# main.net
KiCad netlist of a schematic drawn in Altium Designer
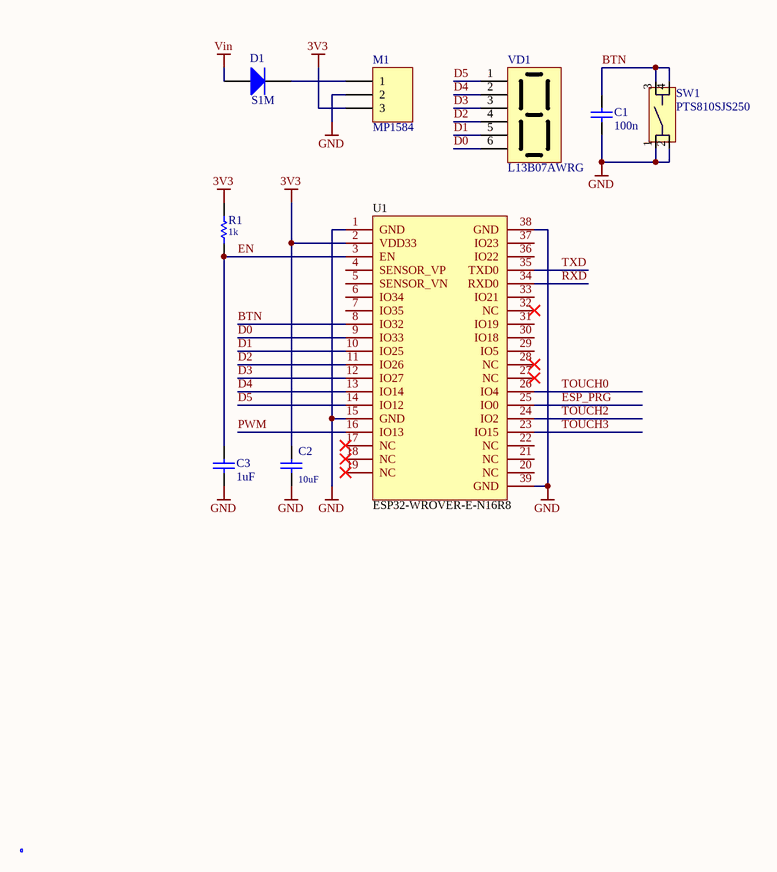
[diagram p0: main.SchDoc]

(export (version "E")
  (design (tool "Eeschema 10.0.6"))
  (components
    (comp (ref "C1")
      (value "100n")
      (footprint "C0402")
      (libsource (lib "Miscellaneous Devices") (part "Cap"))
    )
    (comp (ref "C2")
      (value "10uF")
      (footprint "C0805")
      (libsource (lib "Miscellaneous Devices") (part "CAP"))
    )
    (comp (ref "C3") (value "1uF") (footprint "C1206") (libsource (lib "Miscellaneous Devices") (part "Cap")))
    (comp (ref "D1")
      (value "S1M")
      (footprint "SMA")
      (libsource (lib "Miscellaneous Devices") (part "US1M-13-F"))
    )
    (comp (ref "LOGO1") (value "LOGO") (footprint "LOGO") (libsource (lib "Schlib1") (part "LOGO")))
    (comp (ref "M1")
      (value "MP1584")
      (footprint "MP1584_module")
      (libsource (lib "Miscellaneous Devices") (part "Header 3"))
    )
    (comp (ref "R1")
      (value "1k")
      (footprint "R0603")
      (description "1k 0603")
      (libsource (lib "Miscellaneous Devices") (part "RES"))
    )
    (comp (ref "SW1")
      (value "PTS810SJS250")
      (footprint "BTN_PTS810")
      (fields (field (name "LCSC PART NUMBER") "C221896"))
      (libsource (lib "Miscellaneous Devices") (part "Component_1"))
    )
    (comp (ref "U1")
      (value "ESP32-WROVER-E-N16R8")
      (footprint "WIFIM-SMD_39P-L31.4-W18.0-P1.27")
      (fields (field (name "MANUFACTURER") "ESPRESSIF(乐鑫)"))
      (libsource (lib "Schlib1") (part "ESP32-WROVER-E-N16R8"))
    )
    (comp (ref "VD1")
      (value "L13B07AWRG")
      (footprint "L13B07AWRG")
      (libsource (lib "Schlib1") (part "L13B07AWRG"))
    )
  )
  (nets
    (net (code "1") (name "/BTN") (class "Default")
      (node (ref "C1") (pin "2") (pinfunction "2_2") (pintype "passive"))
      (node (ref "SW1") (pin "3") (pinfunction "3_3") (pintype "passive"))
      (node (ref "SW1") (pin "4") (pinfunction "4_4") (pintype "passive"))
      (node (ref "U1") (pin "8") (pinfunction "IO32_8") (pintype "passive"))
    )
    (net (code "2") (name "/D0") (class "Default")
      (node (ref "U1") (pin "9") (pinfunction "IO33_9") (pintype "passive"))
      (node (ref "VD1") (pin "6") (pinfunction "6_6") (pintype "passive"))
    )
    (net (code "3") (name "/D1") (class "Default")
      (node (ref "U1") (pin "10") (pinfunction "IO25_10") (pintype "passive"))
      (node (ref "VD1") (pin "5") (pinfunction "5_5") (pintype "passive"))
    )
    (net (code "4") (name "/D2") (class "Default")
      (node (ref "U1") (pin "11") (pinfunction "IO26_11") (pintype "passive"))
      (node (ref "VD1") (pin "4") (pinfunction "4_4") (pintype "passive"))
    )
    (net (code "5") (name "/D3") (class "Default")
      (node (ref "U1") (pin "12") (pinfunction "IO27_12") (pintype "passive"))
      (node (ref "VD1") (pin "3") (pinfunction "3_3") (pintype "passive"))
    )
    (net (code "6") (name "/D4") (class "Default")
      (node (ref "U1") (pin "13") (pinfunction "IO14_13") (pintype "passive"))
      (node (ref "VD1") (pin "2") (pinfunction "2_2") (pintype "passive"))
    )
    (net (code "7") (name "/D5") (class "Default")
      (node (ref "U1") (pin "14") (pinfunction "IO12_14") (pintype "passive"))
      (node (ref "VD1") (pin "1") (pinfunction "1_1") (pintype "passive"))
    )
    (net (code "8") (name "/EN") (class "Default")
      (node (ref "C3") (pin "2") (pinfunction "2_2") (pintype "passive"))
      (node (ref "R1") (pin "2") (pinfunction "2_2") (pintype "passive"))
      (node (ref "U1") (pin "3") (pinfunction "EN_3") (pintype "passive"))
    )
    (net (code "9") (name "/ESP_PRG") (class "Default")
      (node (ref "U1") (pin "25") (pinfunction "IO0_25") (pintype "passive"))
    )
    (net (code "10") (name "/PWM") (class "Default")
      (node (ref "U1") (pin "16") (pinfunction "IO13_16") (pintype "passive"))
    )
    (net (code "11") (name "/RXD") (class "Default")
      (node (ref "U1") (pin "34") (pinfunction "RXD0_34") (pintype "passive"))
    )
    (net (code "12") (name "/TOUCH0") (class "Default")
      (node (ref "U1") (pin "26") (pinfunction "IO4_26") (pintype "passive"))
    )
    (net (code "13") (name "/TOUCH2") (class "Default")
      (node (ref "U1") (pin "24") (pinfunction "IO2_24") (pintype "passive"))
    )
    (net (code "14") (name "/TOUCH3") (class "Default")
      (node (ref "U1") (pin "23") (pinfunction "IO15_23") (pintype "passive"))
    )
    (net (code "15") (name "/TXD") (class "Default")
      (node (ref "U1") (pin "35") (pinfunction "TXD0_35") (pintype "passive"))
    )
    (net (code "16") (name "3V3") (class "Default")
      (node (ref "C2") (pin "2") (pinfunction "2_2") (pintype "passive"))
      (node (ref "M1") (pin "3") (pinfunction "3_3") (pintype "passive"))
      (node (ref "R1") (pin "1") (pinfunction "1_1") (pintype "passive"))
      (node (ref "U1") (pin "2") (pinfunction "VDD33_2") (pintype "passive"))
    )
    (net (code "17") (name "GND") (class "Default")
      (node (ref "C1") (pin "1") (pinfunction "1_1") (pintype "passive"))
      (node (ref "C2") (pin "1") (pinfunction "1_1") (pintype "passive"))
      (node (ref "C3") (pin "1") (pinfunction "1_1") (pintype "passive"))
      (node (ref "M1") (pin "2") (pinfunction "2_2") (pintype "passive"))
      (node (ref "SW1") (pin "1") (pinfunction "1_1") (pintype "passive"))
      (node (ref "SW1") (pin "2") (pinfunction "2_2") (pintype "passive"))
      (node (ref "U1") (pin "1") (pinfunction "GND_1") (pintype "passive"))
      (node (ref "U1") (pin "15") (pinfunction "GND_15") (pintype "passive"))
      (node (ref "U1") (pin "38") (pinfunction "GND_38") (pintype "passive"))
      (node (ref "U1") (pin "39") (pinfunction "GND_39") (pintype "passive"))
    )
    (net (code "18") (name "Net-(D1-K)") (class "Default")
      (node (ref "D1") (pin "2") (pinfunction "K_2") (pintype "passive"))
      (node (ref "M1") (pin "1") (pinfunction "1_1") (pintype "passive"))
    )
    (net (code "19") (name "Vin") (class "Default")
      (node (ref "D1") (pin "1") (pinfunction "A_1") (pintype "passive"))
    )
    (net (code "20") (name "unconnected-(U1-IO5-Pad29)") (class "Default")
      (node (ref "U1") (pin "29") (pinfunction "IO5_29") (pintype "passive"))
    )
    (net (code "21") (name "unconnected-(U1-IO18-Pad30)") (class "Default")
      (node (ref "U1") (pin "30") (pinfunction "IO18_30") (pintype "passive"))
    )
    (net (code "22") (name "unconnected-(U1-IO19-Pad31)") (class "Default")
      (node (ref "U1") (pin "31") (pinfunction "IO19_31") (pintype "passive"))
    )
    (net (code "23") (name "unconnected-(U1-IO21-Pad33)") (class "Default")
      (node (ref "U1") (pin "33") (pinfunction "IO21_33") (pintype "passive"))
    )
    (net (code "24") (name "unconnected-(U1-IO22-Pad36)") (class "Default")
      (node (ref "U1") (pin "36") (pinfunction "IO22_36") (pintype "passive"))
    )
    (net (code "25") (name "unconnected-(U1-IO23-Pad37)") (class "Default")
      (node (ref "U1") (pin "37") (pinfunction "IO23_37") (pintype "passive"))
    )
    (net (code "26") (name "unconnected-(U1-IO34-Pad6)") (class "Default")
      (node (ref "U1") (pin "6") (pinfunction "IO34_6") (pintype "passive"))
    )
    (net (code "27") (name "unconnected-(U1-IO35-Pad7)") (class "Default")
      (node (ref "U1") (pin "7") (pinfunction "IO35_7") (pintype "passive"))
    )
    (net (code "28") (name "unconnected-(U1-NC-Pad17)") (class "Default")
      (node (ref "U1") (pin "17") (pinfunction "NC_17") (pintype "passive+no_connect"))
    )
    (net (code "29") (name "unconnected-(U1-NC-Pad18)") (class "Default")
      (node (ref "U1") (pin "18") (pinfunction "NC_18") (pintype "passive+no_connect"))
    )
    (net (code "30") (name "unconnected-(U1-NC-Pad19)") (class "Default")
      (node (ref "U1") (pin "19") (pinfunction "NC_19") (pintype "passive+no_connect"))
    )
    (net (code "31") (name "unconnected-(U1-NC-Pad20)") (class "Default")
      (node (ref "U1") (pin "20") (pinfunction "NC_20") (pintype "passive"))
    )
    (net (code "32") (name "unconnected-(U1-NC-Pad21)") (class "Default")
      (node (ref "U1") (pin "21") (pinfunction "NC_21") (pintype "passive"))
    )
    (net (code "33") (name "unconnected-(U1-NC-Pad22)") (class "Default")
      (node (ref "U1") (pin "22") (pinfunction "NC_22") (pintype "passive"))
    )
    (net (code "34") (name "unconnected-(U1-NC-Pad27)") (class "Default")
      (node (ref "U1") (pin "27") (pinfunction "NC_27") (pintype "passive+no_connect"))
    )
    (net (code "35") (name "unconnected-(U1-NC-Pad28)") (class "Default")
      (node (ref "U1") (pin "28") (pinfunction "NC_28") (pintype "passive+no_connect"))
    )
    (net (code "36") (name "unconnected-(U1-NC-Pad32)") (class "Default")
      (node (ref "U1") (pin "32") (pinfunction "NC_32") (pintype "passive+no_connect"))
    )
    (net (code "37") (name "unconnected-(U1-SENSOR_VN-Pad5)") (class "Default")
      (node (ref "U1") (pin "5") (pinfunction "SENSOR_VN_5") (pintype "passive"))
    )
    (net (code "38") (name "unconnected-(U1-SENSOR_VP-Pad4)") (class "Default")
      (node (ref "U1") (pin "4") (pinfunction "SENSOR_VP_4") (pintype "passive"))
    )
  )
)
